# 4_CV_buffer_design_element.net
KiCad netlist of a schematic drawn in EAGLE
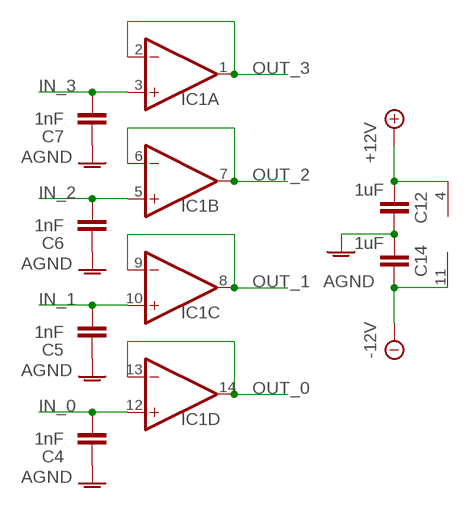
[diagram p0: schematic, sheet 1]

(export (version "E")
  (design (tool "Eeschema 10.0.6"))
  (components
    (comp (ref "C4")
      (value "1nF")
      (footprint "eagle-import:C0603-J")
      (libsource (lib "eagle-import") (part "C-EU-J0603"))
    )
    (comp (ref "C5")
      (value "1nF")
      (footprint "eagle-import:C0603-J")
      (libsource (lib "eagle-import") (part "C-EU-J0603"))
    )
    (comp (ref "C6")
      (value "1nF")
      (footprint "eagle-import:C0603-J")
      (libsource (lib "eagle-import") (part "C-EU-J0603"))
    )
    (comp (ref "C7")
      (value "1nF")
      (footprint "eagle-import:C0603-J")
      (libsource (lib "eagle-import") (part "C-EU-J0603"))
    )
    (comp (ref "C12")
      (value "1uF")
      (footprint "eagle-import:C0402-J")
      (libsource (lib "eagle-import") (part "C-EU-J0402"))
    )
    (comp (ref "C14")
      (value "1uF")
      (footprint "eagle-import:C0402-J")
      (libsource (lib "eagle-import") (part "C-EU-J0402"))
    )
    (comp (ref "IC1")
      (value "TL074JT")
      (footprint "eagle-import:TSSOP14J")
      (libsource (lib "eagle-import") (part "TL074JT"))
    )
  )
  (nets
    (net (code "1") (name "+12V") (class "Default")
      (node (ref "C12") (pin "1") (pinfunction "1_1") (pintype "passive"))
      (node (ref "IC1") (pin "4") (pinfunction "V+_4") (pintype "power_in"))
    )
    (net (code "2") (name "-12V") (class "Default")
      (node (ref "C14") (pin "2") (pinfunction "2_2") (pintype "passive"))
      (node (ref "IC1") (pin "11") (pinfunction "V-_11") (pintype "power_in"))
    )
    (net (code "3") (name "/IN_0") (class "Default")
      (node (ref "C4") (pin "2") (pinfunction "2_2") (pintype "passive"))
      (node (ref "IC1") (pin "12") (pinfunction "+IN_12") (pintype "input"))
    )
    (net (code "4") (name "/IN_1") (class "Default")
      (node (ref "C5") (pin "2") (pinfunction "2_2") (pintype "passive"))
      (node (ref "IC1") (pin "10") (pinfunction "+IN_10") (pintype "input"))
    )
    (net (code "5") (name "/IN_2") (class "Default")
      (node (ref "C6") (pin "2") (pinfunction "2_2") (pintype "passive"))
      (node (ref "IC1") (pin "5") (pinfunction "+IN_5") (pintype "input"))
    )
    (net (code "6") (name "/IN_3") (class "Default")
      (node (ref "C7") (pin "2") (pinfunction "2_2") (pintype "passive"))
      (node (ref "IC1") (pin "3") (pinfunction "+IN_3") (pintype "input"))
    )
    (net (code "7") (name "/OUT_0") (class "Default")
      (node (ref "IC1") (pin "13") (pinfunction "-IN_13") (pintype "input"))
      (node (ref "IC1") (pin "14") (pinfunction "OUT_14") (pintype "output"))
    )
    (net (code "8") (name "/OUT_1") (class "Default")
      (node (ref "IC1") (pin "8") (pinfunction "OUT_8") (pintype "output"))
      (node (ref "IC1") (pin "9") (pinfunction "-IN_9") (pintype "input"))
    )
    (net (code "9") (name "/OUT_2") (class "Default")
      (node (ref "IC1") (pin "6") (pinfunction "-IN_6") (pintype "input"))
      (node (ref "IC1") (pin "7") (pinfunction "OUT_7") (pintype "output"))
    )
    (net (code "10") (name "/OUT_3") (class "Default")
      (node (ref "IC1") (pin "1") (pinfunction "OUT_1") (pintype "output"))
      (node (ref "IC1") (pin "2") (pinfunction "-IN_2") (pintype "input"))
    )
    (net (code "11") (name "AGND") (class "Default")
      (node (ref "C12") (pin "2") (pinfunction "2_2") (pintype "passive"))
      (node (ref "C14") (pin "1") (pinfunction "1_1") (pintype "passive"))
      (node (ref "C4") (pin "1") (pinfunction "1_1") (pintype "passive"))
      (node (ref "C5") (pin "1") (pinfunction "1_1") (pintype "passive"))
      (node (ref "C6") (pin "1") (pinfunction "1_1") (pintype "passive"))
      (node (ref "C7") (pin "1") (pinfunction "1_1") (pintype "passive"))
    )
  )
)
